# External_ADC_and_Reference.net
KiCad netlist of a schematic drawn in Altium Designer
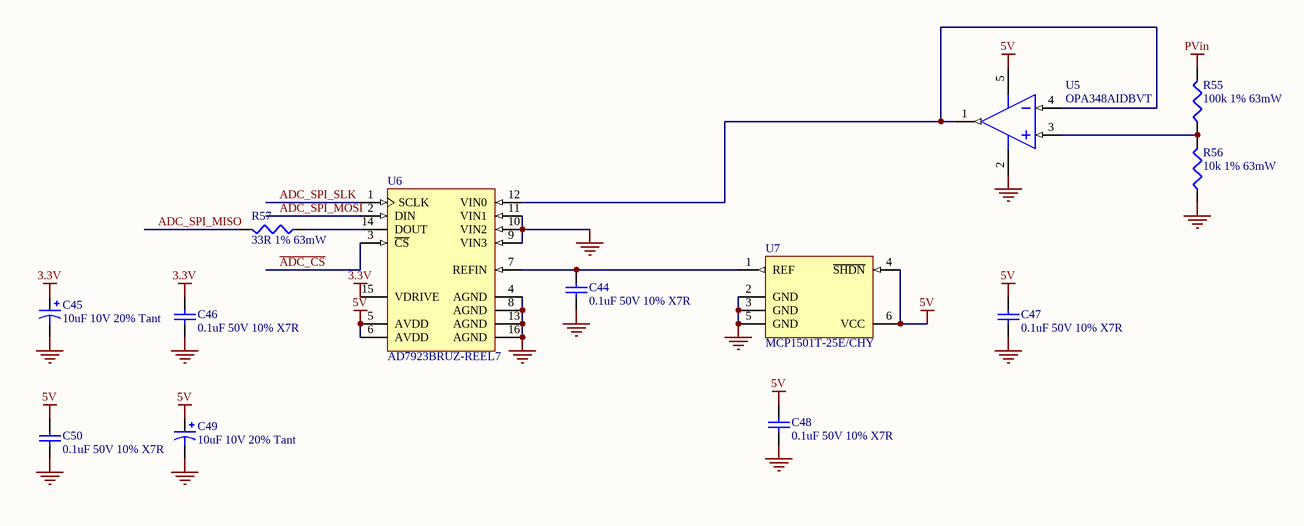
[diagram p0: External ADC and Reference.SchDoc]

(export (version "E")
  (design (tool "Eeschema 10.0.6"))
  (components
    (comp (ref "C44")
      (value "0.1uF 50V 10% X7R")
      (footprint "CAPC1005L")
      (description "Capacitor")
      (libsource (lib "Miscellaneous Devices") (part "Cap"))
    )
    (comp (ref "C45")
      (value "10uF 10V 20% Tant")
      (footprint "C0805")
      (description "CAP TANT 10UF 20% 10V 0805")
      (fields
        (field (name "MANUFACTURER") "AVX Corporation")
        (field (name "MANUFACTURER PART NUMBER") "TLJR106M010R3000")
      )
      (libsource (lib "Miscellaneous Devices") (part "Cap Pol3"))
    )
    (comp (ref "C46")
      (value "0.1uF 50V 10% X7R")
      (footprint "CAPC1005L")
      (description "Capacitor")
      (libsource (lib "Miscellaneous Devices") (part "Cap"))
    )
    (comp (ref "C47")
      (value "0.1uF 50V 10% X7R")
      (footprint "CAPC1005L")
      (description "Capacitor")
      (libsource (lib "Miscellaneous Devices") (part "Cap"))
    )
    (comp (ref "C48")
      (value "0.1uF 50V 10% X7R")
      (footprint "CAPC1005L")
      (description "Capacitor")
      (libsource (lib "Miscellaneous Devices") (part "Cap"))
    )
    (comp (ref "C49")
      (value "10uF 10V 20% Tant")
      (footprint "C0805")
      (description "CAP TANT 10UF 20% 10V 0805")
      (fields
        (field (name "MANUFACTURER") "AVX Corporation")
        (field (name "MANUFACTURER PART NUMBER") "TLJR106M010R3000")
      )
      (libsource (lib "Miscellaneous Devices") (part "Cap Pol3"))
    )
    (comp (ref "C50")
      (value "0.1uF 50V 10% X7R")
      (footprint "CAPC1005L")
      (description "Capacitor")
      (libsource (lib "Miscellaneous Devices") (part "Cap"))
    )
    (comp (ref "R55")
      (value "100k 1% 63mW")
      (footprint "RESC1005L")
      (description "Resistor")
      (libsource (lib "Miscellaneous Devices") (part "Res3"))
    )
    (comp (ref "R56")
      (value "10k 1% 63mW")
      (footprint "RESC1005L")
      (description "Resistor")
      (libsource (lib "Miscellaneous Devices") (part "Res3"))
    )
    (comp (ref "R57")
      (value "33R 1% 63mW")
      (footprint "RESC1005L")
      (description "Resistor")
      (libsource (lib "Miscellaneous Devices") (part "Res3"))
    )
    (comp (ref "U5")
      (value "OPA348AIDBVT")
      (footprint "TI-DBV5_L")
      (description "IC OPAMP GP 1 CIRCUIT SOT23-5")
      (fields (field (name "MANUFACTURER") "Texas Instruments"))
      (libsource (lib "TI Amplifiers and Linear Operational Amplifier Precision Amplifier Part One") (part "OPA348AIDBVT"))
    )
    (comp (ref "U6")
      (value "AD7923BRUZ-REEL7")
      (footprint "RU-16_L")
      (description "IC ADC 12BIT SAR 16TSSOP")
      (fields (field (name "MANUFACTURER") "Analog Devices Inc"))
      (libsource (lib "Analog Devices Data Converters Analog-to-Digital Converters") (part "AD7923BRUZ-REEL7"))
    )
    (comp (ref "U7")
      (value "MCP1501T-25E/CHY")
      (footprint "SOT23-6_L")
      (description "IC VREF SERIES 0.1% SOT23-6")
      (fields (field (name "MANUFACTURER") "Microchip Technology"))
      (libsource (lib "Maxim Sensors") (part "MAX6610AUT+"))
    )
  )
  (nets
    (net (code "1") (name "/ADC_SPI_MISO") (class "Default")
      (node (ref "R57") (pin "2") (pinfunction "2_2") (pintype "passive"))
    )
    (net (code "2") (name "/ADC_SPI_MOSI") (class "Default")
      (node (ref "U6") (pin "2") (pinfunction "DIN_2") (pintype "input"))
    )
    (net (code "3") (name "/ADC_SPI_SLK") (class "Default")
      (node (ref "U6") (pin "1") (pinfunction "SCLK_1") (pintype "input"))
    )
    (net (code "4") (name "/~{ADC_CS}") (class "Default")
      (node (ref "U6") (pin "3") (pinfunction "~{CS}_3") (pintype "input"))
    )
    (net (code "5") (name "3.3V") (class "Default")
      (node (ref "C45") (pin "1") (pinfunction "1_1") (pintype "passive"))
      (node (ref "C46") (pin "1") (pinfunction "1_1") (pintype "passive"))
      (node (ref "U6") (pin "15") (pinfunction "VDRIVE_15") (pintype "power_in"))
    )
    (net (code "6") (name "5V") (class "Default")
      (node (ref "C47") (pin "1") (pinfunction "1_1") (pintype "passive"))
      (node (ref "C48") (pin "1") (pinfunction "1_1") (pintype "passive"))
      (node (ref "C49") (pin "1") (pinfunction "1_1") (pintype "passive"))
      (node (ref "C50") (pin "1") (pinfunction "1_1") (pintype "passive"))
      (node (ref "U5") (pin "5") (pinfunction "V+_5") (pintype "power_in"))
      (node (ref "U6") (pin "5") (pinfunction "AVDD_5") (pintype "power_in"))
      (node (ref "U6") (pin "6") (pinfunction "AVDD_6") (pintype "power_in"))
      (node (ref "U7") (pin "4") (pinfunction "~{SHDN}_4") (pintype "input"))
      (node (ref "U7") (pin "6") (pinfunction "VCC_6") (pintype "power_in"))
    )
    (net (code "7") (name "GND") (class "Default")
      (node (ref "C44") (pin "2") (pinfunction "2_2") (pintype "passive"))
      (node (ref "C45") (pin "2") (pinfunction "2_2") (pintype "passive"))
      (node (ref "C46") (pin "2") (pinfunction "2_2") (pintype "passive"))
      (node (ref "C47") (pin "2") (pinfunction "2_2") (pintype "passive"))
      (node (ref "C48") (pin "2") (pinfunction "2_2") (pintype "passive"))
      (node (ref "C49") (pin "2") (pinfunction "2_2") (pintype "passive"))
      (node (ref "C50") (pin "2") (pinfunction "2_2") (pintype "passive"))
      (node (ref "R56") (pin "1") (pinfunction "1_1") (pintype "passive"))
      (node (ref "U5") (pin "2") (pinfunction "V-_2") (pintype "power_in"))
      (node (ref "U6") (pin "10") (pinfunction "VIN2_10") (pintype "input"))
      (node (ref "U6") (pin "11") (pinfunction "VIN1_11") (pintype "input"))
      (node (ref "U6") (pin "13") (pinfunction "AGND_13") (pintype "power_in"))
      (node (ref "U6") (pin "16") (pinfunction "AGND_16") (pintype "power_in"))
      (node (ref "U6") (pin "4") (pinfunction "AGND_4") (pintype "power_in"))
      (node (ref "U6") (pin "8") (pinfunction "AGND_8") (pintype "power_in"))
      (node (ref "U6") (pin "9") (pinfunction "VIN3_9") (pintype "input"))
      (node (ref "U7") (pin "2") (pinfunction "GND_2") (pintype "power_in"))
      (node (ref "U7") (pin "3") (pinfunction "GND_3") (pintype "power_in"))
      (node (ref "U7") (pin "5") (pinfunction "GND_5") (pintype "power_in"))
    )
    (net (code "8") (name "Net-(U5-IN+)") (class "Default")
      (node (ref "R55") (pin "1") (pinfunction "1_1") (pintype "passive"))
      (node (ref "R56") (pin "2") (pinfunction "2_2") (pintype "passive"))
      (node (ref "U5") (pin "3") (pinfunction "IN+_3") (pintype "input"))
    )
    (net (code "9") (name "Net-(U5-IN-)") (class "Default")
      (node (ref "U5") (pin "1") (pinfunction "OUT_1") (pintype "output"))
      (node (ref "U5") (pin "4") (pinfunction "IN-_4") (pintype "input"))
      (node (ref "U6") (pin "12") (pinfunction "VIN0_12") (pintype "input"))
    )
    (net (code "10") (name "Net-(U6-DOUT)") (class "Default")
      (node (ref "R57") (pin "1") (pinfunction "1_1") (pintype "passive"))
      (node (ref "U6") (pin "14") (pinfunction "DOUT_14") (pintype "tri_state"))
    )
    (net (code "11") (name "Net-(U6-REFIN)") (class "Default")
      (node (ref "C44") (pin "1") (pinfunction "1_1") (pintype "passive"))
      (node (ref "U6") (pin "7") (pinfunction "REFIN_7") (pintype "input"))
      (node (ref "U7") (pin "1") (pinfunction "REF_1") (pintype "output"))
    )
    (net (code "12") (name "PVin") (class "Default")
      (node (ref "R55") (pin "2") (pinfunction "2_2") (pintype "passive"))
    )
  )
)
